# HeatPlates.net
KiCad netlist of a schematic drawn in Altium Designer
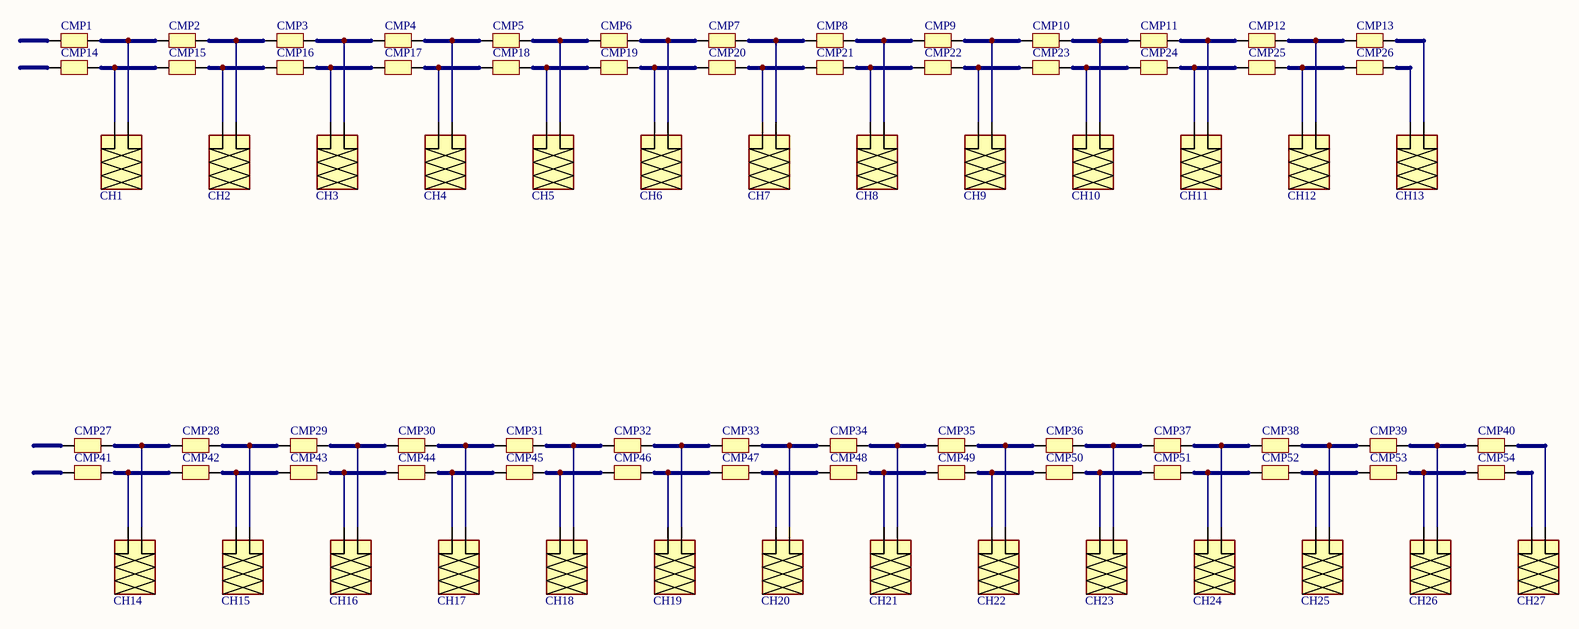
[diagram p0: HeatPlates.SchDoc]

(export (version "E")
  (design (tool "Eeschema 10.0.6"))
  (components
    (comp (ref "CH1")
      (value "GCH")
      (footprint "Generic Cartridge Heater-Footprint-1")
      (description "Generic cartridge heater")
      (libsource (lib "IIT Motorsports") (part "GCH-Symbol-1"))
    )
    (comp (ref "CH2")
      (value "GCH")
      (footprint "Generic Cartridge Heater-Footprint-1")
      (description "Generic cartridge heater")
      (libsource (lib "IIT Motorsports") (part "GCH-Symbol-1"))
    )
    (comp (ref "CH3")
      (value "GCH")
      (footprint "Generic Cartridge Heater-Footprint-1")
      (description "Generic cartridge heater")
      (libsource (lib "IIT Motorsports") (part "GCH-Symbol-1"))
    )
    (comp (ref "CH4")
      (value "GCH")
      (footprint "Generic Cartridge Heater-Footprint-1")
      (description "Generic cartridge heater")
      (libsource (lib "IIT Motorsports") (part "GCH-Symbol-1"))
    )
    (comp (ref "CH5")
      (value "GCH")
      (footprint "Generic Cartridge Heater-Footprint-1")
      (description "Generic cartridge heater")
      (libsource (lib "IIT Motorsports") (part "GCH-Symbol-1"))
    )
    (comp (ref "CH6")
      (value "GCH")
      (footprint "Generic Cartridge Heater-Footprint-1")
      (description "Generic cartridge heater")
      (libsource (lib "IIT Motorsports") (part "GCH-Symbol-1"))
    )
    (comp (ref "CH7")
      (value "GCH")
      (footprint "Generic Cartridge Heater-Footprint-1")
      (description "Generic cartridge heater")
      (libsource (lib "IIT Motorsports") (part "GCH-Symbol-1"))
    )
    (comp (ref "CH8")
      (value "GCH")
      (footprint "Generic Cartridge Heater-Footprint-1")
      (description "Generic cartridge heater")
      (libsource (lib "IIT Motorsports") (part "GCH-Symbol-1"))
    )
    (comp (ref "CH9")
      (value "GCH")
      (footprint "Generic Cartridge Heater-Footprint-1")
      (description "Generic cartridge heater")
      (libsource (lib "IIT Motorsports") (part "GCH-Symbol-1"))
    )
    (comp (ref "CH10")
      (value "GCH")
      (footprint "Generic Cartridge Heater-Footprint-1")
      (description "Generic cartridge heater")
      (libsource (lib "IIT Motorsports") (part "GCH-Symbol-1"))
    )
    (comp (ref "CH11")
      (value "GCH")
      (footprint "Generic Cartridge Heater-Footprint-1")
      (description "Generic cartridge heater")
      (libsource (lib "IIT Motorsports") (part "GCH-Symbol-1"))
    )
    (comp (ref "CH12")
      (value "GCH")
      (footprint "Generic Cartridge Heater-Footprint-1")
      (description "Generic cartridge heater")
      (libsource (lib "IIT Motorsports") (part "GCH-Symbol-1"))
    )
    (comp (ref "CH13")
      (value "GCH")
      (footprint "Generic Cartridge Heater-Footprint-1")
      (description "Generic cartridge heater")
      (libsource (lib "IIT Motorsports") (part "GCH-Symbol-1"))
    )
    (comp (ref "CH14")
      (value "GCH")
      (footprint "Generic Cartridge Heater-Footprint-1")
      (description "Generic cartridge heater")
      (libsource (lib "IIT Motorsports") (part "GCH-Symbol-1"))
    )
    (comp (ref "CH15")
      (value "GCH")
      (footprint "Generic Cartridge Heater-Footprint-1")
      (description "Generic cartridge heater")
      (libsource (lib "IIT Motorsports") (part "GCH-Symbol-1"))
    )
    (comp (ref "CH16")
      (value "GCH")
      (footprint "Generic Cartridge Heater-Footprint-1")
      (description "Generic cartridge heater")
      (libsource (lib "IIT Motorsports") (part "GCH-Symbol-1"))
    )
    (comp (ref "CH17")
      (value "GCH")
      (footprint "Generic Cartridge Heater-Footprint-1")
      (description "Generic cartridge heater")
      (libsource (lib "IIT Motorsports") (part "GCH-Symbol-1"))
    )
    (comp (ref "CH18")
      (value "GCH")
      (footprint "Generic Cartridge Heater-Footprint-1")
      (description "Generic cartridge heater")
      (libsource (lib "IIT Motorsports") (part "GCH-Symbol-1"))
    )
    (comp (ref "CH19")
      (value "GCH")
      (footprint "Generic Cartridge Heater-Footprint-1")
      (description "Generic cartridge heater")
      (libsource (lib "IIT Motorsports") (part "GCH-Symbol-1"))
    )
    (comp (ref "CH20")
      (value "GCH")
      (footprint "Generic Cartridge Heater-Footprint-1")
      (description "Generic cartridge heater")
      (libsource (lib "IIT Motorsports") (part "GCH-Symbol-1"))
    )
    (comp (ref "CH21")
      (value "GCH")
      (footprint "Generic Cartridge Heater-Footprint-1")
      (description "Generic cartridge heater")
      (libsource (lib "IIT Motorsports") (part "GCH-Symbol-1"))
    )
    (comp (ref "CH22")
      (value "GCH")
      (footprint "Generic Cartridge Heater-Footprint-1")
      (description "Generic cartridge heater")
      (libsource (lib "IIT Motorsports") (part "GCH-Symbol-1"))
    )
    (comp (ref "CH23")
      (value "GCH")
      (footprint "Generic Cartridge Heater-Footprint-1")
      (description "Generic cartridge heater")
      (libsource (lib "IIT Motorsports") (part "GCH-Symbol-1"))
    )
    (comp (ref "CH24")
      (value "GCH")
      (footprint "Generic Cartridge Heater-Footprint-1")
      (description "Generic cartridge heater")
      (libsource (lib "IIT Motorsports") (part "GCH-Symbol-1"))
    )
    (comp (ref "CH25")
      (value "GCH")
      (footprint "Generic Cartridge Heater-Footprint-1")
      (description "Generic cartridge heater")
      (libsource (lib "IIT Motorsports") (part "GCH-Symbol-1"))
    )
    (comp (ref "CH26")
      (value "GCH")
      (footprint "Generic Cartridge Heater-Footprint-1")
      (description "Generic cartridge heater")
      (libsource (lib "IIT Motorsports") (part "GCH-Symbol-1"))
    )
    (comp (ref "CH27")
      (value "GCH")
      (footprint "Generic Cartridge Heater-Footprint-1")
      (description "Generic cartridge heater")
      (libsource (lib "IIT Motorsports") (part "GCH-Symbol-1"))
    )
    (comp (ref "CMP1")
      (value "0192020054")
      (footprint "0192020054-Footprint-1")
      (libsource (lib "IIT Motorsports") (part "0192020054-Symbol-1"))
    )
    (comp (ref "CMP2")
      (value "0192020054")
      (footprint "0192020054-Footprint-1")
      (libsource (lib "IIT Motorsports") (part "0192020054-Symbol-1"))
    )
    (comp (ref "CMP3")
      (value "0192020054")
      (footprint "0192020054-Footprint-1")
      (libsource (lib "IIT Motorsports") (part "0192020054-Symbol-1"))
    )
    (comp (ref "CMP4")
      (value "0192020054")
      (footprint "0192020054-Footprint-1")
      (libsource (lib "IIT Motorsports") (part "0192020054-Symbol-1"))
    )
    (comp (ref "CMP5")
      (value "0192020054")
      (footprint "0192020054-Footprint-1")
      (libsource (lib "IIT Motorsports") (part "0192020054-Symbol-1"))
    )
    (comp (ref "CMP6")
      (value "0192020054")
      (footprint "0192020054-Footprint-1")
      (libsource (lib "IIT Motorsports") (part "0192020054-Symbol-1"))
    )
    (comp (ref "CMP7")
      (value "0192020054")
      (footprint "0192020054-Footprint-1")
      (libsource (lib "IIT Motorsports") (part "0192020054-Symbol-1"))
    )
    (comp (ref "CMP8")
      (value "0192020054")
      (footprint "0192020054-Footprint-1")
      (libsource (lib "IIT Motorsports") (part "0192020054-Symbol-1"))
    )
    (comp (ref "CMP9")
      (value "0192020054")
      (footprint "0192020054-Footprint-1")
      (libsource (lib "IIT Motorsports") (part "0192020054-Symbol-1"))
    )
    (comp (ref "CMP10")
      (value "0192020054")
      (footprint "0192020054-Footprint-1")
      (libsource (lib "IIT Motorsports") (part "0192020054-Symbol-1"))
    )
    (comp (ref "CMP11")
      (value "0192020054")
      (footprint "0192020054-Footprint-1")
      (libsource (lib "IIT Motorsports") (part "0192020054-Symbol-1"))
    )
    (comp (ref "CMP12")
      (value "0192020054")
      (footprint "0192020054-Footprint-1")
      (libsource (lib "IIT Motorsports") (part "0192020054-Symbol-1"))
    )
    (comp (ref "CMP13")
      (value "0192020054")
      (footprint "0192020054-Footprint-1")
      (libsource (lib "IIT Motorsports") (part "0192020054-Symbol-1"))
    )
    (comp (ref "CMP14")
      (value "0192020054")
      (footprint "0192020054-Footprint-1")
      (libsource (lib "IIT Motorsports") (part "0192020054-Symbol-1"))
    )
    (comp (ref "CMP15")
      (value "0192020054")
      (footprint "0192020054-Footprint-1")
      (libsource (lib "IIT Motorsports") (part "0192020054-Symbol-1"))
    )
    (comp (ref "CMP16")
      (value "0192020054")
      (footprint "0192020054-Footprint-1")
      (libsource (lib "IIT Motorsports") (part "0192020054-Symbol-1"))
    )
    (comp (ref "CMP17")
      (value "0192020054")
      (footprint "0192020054-Footprint-1")
      (libsource (lib "IIT Motorsports") (part "0192020054-Symbol-1"))
    )
    (comp (ref "CMP18")
      (value "0192020054")
      (footprint "0192020054-Footprint-1")
      (libsource (lib "IIT Motorsports") (part "0192020054-Symbol-1"))
    )
    (comp (ref "CMP19")
      (value "0192020054")
      (footprint "0192020054-Footprint-1")
      (libsource (lib "IIT Motorsports") (part "0192020054-Symbol-1"))
    )
    (comp (ref "CMP20")
      (value "0192020054")
      (footprint "0192020054-Footprint-1")
      (libsource (lib "IIT Motorsports") (part "0192020054-Symbol-1"))
    )
    (comp (ref "CMP21")
      (value "0192020054")
      (footprint "0192020054-Footprint-1")
      (libsource (lib "IIT Motorsports") (part "0192020054-Symbol-1"))
    )
    (comp (ref "CMP22")
      (value "0192020054")
      (footprint "0192020054-Footprint-1")
      (libsource (lib "IIT Motorsports") (part "0192020054-Symbol-1"))
    )
    (comp (ref "CMP23")
      (value "0192020054")
      (footprint "0192020054-Footprint-1")
      (libsource (lib "IIT Motorsports") (part "0192020054-Symbol-1"))
    )
    (comp (ref "CMP24")
      (value "0192020054")
      (footprint "0192020054-Footprint-1")
      (libsource (lib "IIT Motorsports") (part "0192020054-Symbol-1"))
    )
    (comp (ref "CMP25")
      (value "0192020054")
      (footprint "0192020054-Footprint-1")
      (libsource (lib "IIT Motorsports") (part "0192020054-Symbol-1"))
    )
    (comp (ref "CMP26")
      (value "0192020054")
      (footprint "0192020054-Footprint-1")
      (libsource (lib "IIT Motorsports") (part "0192020054-Symbol-1"))
    )
    (comp (ref "CMP27")
      (value "0192020054")
      (footprint "0192020054-Footprint-1")
      (libsource (lib "IIT Motorsports") (part "0192020054-Symbol-1"))
    )
    (comp (ref "CMP28")
      (value "0192020054")
      (footprint "0192020054-Footprint-1")
      (libsource (lib "IIT Motorsports") (part "0192020054-Symbol-1"))
    )
    (comp (ref "CMP29")
      (value "0192020054")
      (footprint "0192020054-Footprint-1")
      (libsource (lib "IIT Motorsports") (part "0192020054-Symbol-1"))
    )
    (comp (ref "CMP30")
      (value "0192020054")
      (footprint "0192020054-Footprint-1")
      (libsource (lib "IIT Motorsports") (part "0192020054-Symbol-1"))
    )
    (comp (ref "CMP31")
      (value "0192020054")
      (footprint "0192020054-Footprint-1")
      (libsource (lib "IIT Motorsports") (part "0192020054-Symbol-1"))
    )
    (comp (ref "CMP32")
      (value "0192020054")
      (footprint "0192020054-Footprint-1")
      (libsource (lib "IIT Motorsports") (part "0192020054-Symbol-1"))
    )
    (comp (ref "CMP33")
      (value "0192020054")
      (footprint "0192020054-Footprint-1")
      (libsource (lib "IIT Motorsports") (part "0192020054-Symbol-1"))
    )
    (comp (ref "CMP34")
      (value "0192020054")
      (footprint "0192020054-Footprint-1")
      (libsource (lib "IIT Motorsports") (part "0192020054-Symbol-1"))
    )
    (comp (ref "CMP35")
      (value "0192020054")
      (footprint "0192020054-Footprint-1")
      (libsource (lib "IIT Motorsports") (part "0192020054-Symbol-1"))
    )
    (comp (ref "CMP36")
      (value "0192020054")
      (footprint "0192020054-Footprint-1")
      (libsource (lib "IIT Motorsports") (part "0192020054-Symbol-1"))
    )
    (comp (ref "CMP37")
      (value "0192020054")
      (footprint "0192020054-Footprint-1")
      (libsource (lib "IIT Motorsports") (part "0192020054-Symbol-1"))
    )
    (comp (ref "CMP38")
      (value "0192020054")
      (footprint "0192020054-Footprint-1")
      (libsource (lib "IIT Motorsports") (part "0192020054-Symbol-1"))
    )
    (comp (ref "CMP39")
      (value "0192020054")
      (footprint "0192020054-Footprint-1")
      (libsource (lib "IIT Motorsports") (part "0192020054-Symbol-1"))
    )
    (comp (ref "CMP40")
      (value "0192020054")
      (footprint "0192020054-Footprint-1")
      (libsource (lib "IIT Motorsports") (part "0192020054-Symbol-1"))
    )
    (comp (ref "CMP41")
      (value "0192020054")
      (footprint "0192020054-Footprint-1")
      (libsource (lib "IIT Motorsports") (part "0192020054-Symbol-1"))
    )
    (comp (ref "CMP42")
      (value "0192020054")
      (footprint "0192020054-Footprint-1")
      (libsource (lib "IIT Motorsports") (part "0192020054-Symbol-1"))
    )
    (comp (ref "CMP43")
      (value "0192020054")
      (footprint "0192020054-Footprint-1")
      (libsource (lib "IIT Motorsports") (part "0192020054-Symbol-1"))
    )
    (comp (ref "CMP44")
      (value "0192020054")
      (footprint "0192020054-Footprint-1")
      (libsource (lib "IIT Motorsports") (part "0192020054-Symbol-1"))
    )
    (comp (ref "CMP45")
      (value "0192020054")
      (footprint "0192020054-Footprint-1")
      (libsource (lib "IIT Motorsports") (part "0192020054-Symbol-1"))
    )
    (comp (ref "CMP46")
      (value "0192020054")
      (footprint "0192020054-Footprint-1")
      (libsource (lib "IIT Motorsports") (part "0192020054-Symbol-1"))
    )
    (comp (ref "CMP47")
      (value "0192020054")
      (footprint "0192020054-Footprint-1")
      (libsource (lib "IIT Motorsports") (part "0192020054-Symbol-1"))
    )
    (comp (ref "CMP48")
      (value "0192020054")
      (footprint "0192020054-Footprint-1")
      (libsource (lib "IIT Motorsports") (part "0192020054-Symbol-1"))
    )
    (comp (ref "CMP49")
      (value "0192020054")
      (footprint "0192020054-Footprint-1")
      (libsource (lib "IIT Motorsports") (part "0192020054-Symbol-1"))
    )
    (comp (ref "CMP50")
      (value "0192020054")
      (footprint "0192020054-Footprint-1")
      (libsource (lib "IIT Motorsports") (part "0192020054-Symbol-1"))
    )
    (comp (ref "CMP51")
      (value "0192020054")
      (footprint "0192020054-Footprint-1")
      (libsource (lib "IIT Motorsports") (part "0192020054-Symbol-1"))
    )
    (comp (ref "CMP52")
      (value "0192020054")
      (footprint "0192020054-Footprint-1")
      (libsource (lib "IIT Motorsports") (part "0192020054-Symbol-1"))
    )
    (comp (ref "CMP53")
      (value "0192020054")
      (footprint "0192020054-Footprint-1")
      (libsource (lib "IIT Motorsports") (part "0192020054-Symbol-1"))
    )
    (comp (ref "CMP54")
      (value "0192020054")
      (footprint "0192020054-Footprint-1")
      (libsource (lib "IIT Motorsports") (part "0192020054-Symbol-1"))
    )
  )
  (nets
    (net (code "1") (name "Net-(CH1-Pad0)") (class "Default")
      (node (ref "CH1") (pin "0") (pinfunction "0_0") (pintype "passive"))
      (node (ref "CMP14") (pin "1") (pinfunction "1_1") (pintype "passive"))
      (node (ref "CMP15") (pin "0") (pinfunction "0_0") (pintype "passive"))
    )
    (net (code "2") (name "Net-(CH1-Pad1)") (class "Default")
      (node (ref "CH1") (pin "1") (pinfunction "1_1") (pintype "passive"))
      (node (ref "CMP1") (pin "1") (pinfunction "1_1") (pintype "passive"))
      (node (ref "CMP2") (pin "0") (pinfunction "0_0") (pintype "passive"))
    )
    (net (code "3") (name "Net-(CH2-Pad0)") (class "Default")
      (node (ref "CH2") (pin "0") (pinfunction "0_0") (pintype "passive"))
      (node (ref "CMP15") (pin "1") (pinfunction "1_1") (pintype "passive"))
      (node (ref "CMP16") (pin "0") (pinfunction "0_0") (pintype "passive"))
    )
    (net (code "4") (name "Net-(CH2-Pad1)") (class "Default")
      (node (ref "CH2") (pin "1") (pinfunction "1_1") (pintype "passive"))
      (node (ref "CMP2") (pin "1") (pinfunction "1_1") (pintype "passive"))
      (node (ref "CMP3") (pin "0") (pinfunction "0_0") (pintype "passive"))
    )
    (net (code "5") (name "Net-(CH3-Pad0)") (class "Default")
      (node (ref "CH3") (pin "0") (pinfunction "0_0") (pintype "passive"))
      (node (ref "CMP16") (pin "1") (pinfunction "1_1") (pintype "passive"))
      (node (ref "CMP17") (pin "0") (pinfunction "0_0") (pintype "passive"))
    )
    (net (code "6") (name "Net-(CH3-Pad1)") (class "Default")
      (node (ref "CH3") (pin "1") (pinfunction "1_1") (pintype "passive"))
      (node (ref "CMP3") (pin "1") (pinfunction "1_1") (pintype "passive"))
      (node (ref "CMP4") (pin "0") (pinfunction "0_0") (pintype "passive"))
    )
    (net (code "7") (name "Net-(CH4-Pad0)") (class "Default")
      (node (ref "CH4") (pin "0") (pinfunction "0_0") (pintype "passive"))
      (node (ref "CMP17") (pin "1") (pinfunction "1_1") (pintype "passive"))
      (node (ref "CMP18") (pin "0") (pinfunction "0_0") (pintype "passive"))
    )
    (net (code "8") (name "Net-(CH4-Pad1)") (class "Default")
      (node (ref "CH4") (pin "1") (pinfunction "1_1") (pintype "passive"))
      (node (ref "CMP4") (pin "1") (pinfunction "1_1") (pintype "passive"))
      (node (ref "CMP5") (pin "0") (pinfunction "0_0") (pintype "passive"))
    )
    (net (code "9") (name "Net-(CH5-Pad0)") (class "Default")
      (node (ref "CH5") (pin "0") (pinfunction "0_0") (pintype "passive"))
      (node (ref "CMP18") (pin "1") (pinfunction "1_1") (pintype "passive"))
      (node (ref "CMP19") (pin "0") (pinfunction "0_0") (pintype "passive"))
    )
    (net (code "10") (name "Net-(CH5-Pad1)") (class "Default")
      (node (ref "CH5") (pin "1") (pinfunction "1_1") (pintype "passive"))
      (node (ref "CMP5") (pin "1") (pinfunction "1_1") (pintype "passive"))
      (node (ref "CMP6") (pin "0") (pinfunction "0_0") (pintype "passive"))
    )
    (net (code "11") (name "Net-(CH6-Pad0)") (class "Default")
      (node (ref "CH6") (pin "0") (pinfunction "0_0") (pintype "passive"))
      (node (ref "CMP19") (pin "1") (pinfunction "1_1") (pintype "passive"))
      (node (ref "CMP20") (pin "0") (pinfunction "0_0") (pintype "passive"))
    )
    (net (code "12") (name "Net-(CH6-Pad1)") (class "Default")
      (node (ref "CH6") (pin "1") (pinfunction "1_1") (pintype "passive"))
      (node (ref "CMP6") (pin "1") (pinfunction "1_1") (pintype "passive"))
      (node (ref "CMP7") (pin "0") (pinfunction "0_0") (pintype "passive"))
    )
    (net (code "13") (name "Net-(CH7-Pad0)") (class "Default")
      (node (ref "CH7") (pin "0") (pinfunction "0_0") (pintype "passive"))
      (node (ref "CMP20") (pin "1") (pinfunction "1_1") (pintype "passive"))
      (node (ref "CMP21") (pin "0") (pinfunction "0_0") (pintype "passive"))
    )
    (net (code "14") (name "Net-(CH7-Pad1)") (class "Default")
      (node (ref "CH7") (pin "1") (pinfunction "1_1") (pintype "passive"))
      (node (ref "CMP7") (pin "1") (pinfunction "1_1") (pintype "passive"))
      (node (ref "CMP8") (pin "0") (pinfunction "0_0") (pintype "passive"))
    )
    (net (code "15") (name "Net-(CH8-Pad0)") (class "Default")
      (node (ref "CH8") (pin "0") (pinfunction "0_0") (pintype "passive"))
      (node (ref "CMP21") (pin "1") (pinfunction "1_1") (pintype "passive"))
      (node (ref "CMP22") (pin "0") (pinfunction "0_0") (pintype "passive"))
    )
    (net (code "16") (name "Net-(CH8-Pad1)") (class "Default")
      (node (ref "CH8") (pin "1") (pinfunction "1_1") (pintype "passive"))
      (node (ref "CMP8") (pin "1") (pinfunction "1_1") (pintype "passive"))
      (node (ref "CMP9") (pin "0") (pinfunction "0_0") (pintype "passive"))
    )
    (net (code "17") (name "Net-(CH9-Pad0)") (class "Default")
      (node (ref "CH9") (pin "0") (pinfunction "0_0") (pintype "passive"))
      (node (ref "CMP22") (pin "1") (pinfunction "1_1") (pintype "passive"))
      (node (ref "CMP23") (pin "0") (pinfunction "0_0") (pintype "passive"))
    )
    (net (code "18") (name "Net-(CH9-Pad1)") (class "Default")
      (node (ref "CH9") (pin "1") (pinfunction "1_1") (pintype "passive"))
      (node (ref "CMP10") (pin "0") (pinfunction "0_0") (pintype "passive"))
      (node (ref "CMP9") (pin "1") (pinfunction "1_1") (pintype "passive"))
    )
    (net (code "19") (name "Net-(CH10-Pad0)") (class "Default")
      (node (ref "CH10") (pin "0") (pinfunction "0_0") (pintype "passive"))
      (node (ref "CMP23") (pin "1") (pinfunction "1_1") (pintype "passive"))
      (node (ref "CMP24") (pin "0") (pinfunction "0_0") (pintype "passive"))
    )
    (net (code "20") (name "Net-(CH10-Pad1)") (class "Default")
      (node (ref "CH10") (pin "1") (pinfunction "1_1") (pintype "passive"))
      (node (ref "CMP10") (pin "1") (pinfunction "1_1") (pintype "passive"))
      (node (ref "CMP11") (pin "0") (pinfunction "0_0") (pintype "passive"))
    )
    (net (code "21") (name "Net-(CH11-Pad0)") (class "Default")
      (node (ref "CH11") (pin "0") (pinfunction "0_0") (pintype "passive"))
      (node (ref "CMP24") (pin "1") (pinfunction "1_1") (pintype "passive"))
      (node (ref "CMP25") (pin "0") (pinfunction "0_0") (pintype "passive"))
    )
    (net (code "22") (name "Net-(CH11-Pad1)") (class "Default")
      (node (ref "CH11") (pin "1") (pinfunction "1_1") (pintype "passive"))
      (node (ref "CMP11") (pin "1") (pinfunction "1_1") (pintype "passive"))
      (node (ref "CMP12") (pin "0") (pinfunction "0_0") (pintype "passive"))
    )
    (net (code "23") (name "Net-(CH12-Pad0)") (class "Default")
      (node (ref "CH12") (pin "0") (pinfunction "0_0") (pintype "passive"))
      (node (ref "CMP25") (pin "1") (pinfunction "1_1") (pintype "passive"))
      (node (ref "CMP26") (pin "0") (pinfunction "0_0") (pintype "passive"))
    )
    (net (code "24") (name "Net-(CH12-Pad1)") (class "Default")
      (node (ref "CH12") (pin "1") (pinfunction "1_1") (pintype "passive"))
      (node (ref "CMP12") (pin "1") (pinfunction "1_1") (pintype "passive"))
      (node (ref "CMP13") (pin "0") (pinfunction "0_0") (pintype "passive"))
    )
    (net (code "25") (name "Net-(CH13-Pad0)") (class "Default")
      (node (ref "CH13") (pin "0") (pinfunction "0_0") (pintype "passive"))
      (node (ref "CMP26") (pin "1") (pinfunction "1_1") (pintype "passive"))
    )
    (net (code "26") (name "Net-(CH13-Pad1)") (class "Default")
      (node (ref "CH13") (pin "1") (pinfunction "1_1") (pintype "passive"))
      (node (ref "CMP13") (pin "1") (pinfunction "1_1") (pintype "passive"))
    )
    (net (code "27") (name "Net-(CH14-Pad0)") (class "Default")
      (node (ref "CH14") (pin "0") (pinfunction "0_0") (pintype "passive"))
      (node (ref "CMP41") (pin "1") (pinfunction "1_1") (pintype "passive"))
      (node (ref "CMP42") (pin "0") (pinfunction "0_0") (pintype "passive"))
    )
    (net (code "28") (name "Net-(CH14-Pad1)") (class "Default")
      (node (ref "CH14") (pin "1") (pinfunction "1_1") (pintype "passive"))
      (node (ref "CMP27") (pin "1") (pinfunction "1_1") (pintype "passive"))
      (node (ref "CMP28") (pin "0") (pinfunction "0_0") (pintype "passive"))
    )
    (net (code "29") (name "Net-(CH15-Pad0)") (class "Default")
      (node (ref "CH15") (pin "0") (pinfunction "0_0") (pintype "passive"))
      (node (ref "CMP42") (pin "1") (pinfunction "1_1") (pintype "passive"))
      (node (ref "CMP43") (pin "0") (pinfunction "0_0") (pintype "passive"))
    )
    (net (code "30") (name "Net-(CH15-Pad1)") (class "Default")
      (node (ref "CH15") (pin "1") (pinfunction "1_1") (pintype "passive"))
      (node (ref "CMP28") (pin "1") (pinfunction "1_1") (pintype "passive"))
      (node (ref "CMP29") (pin "0") (pinfunction "0_0") (pintype "passive"))
    )
    (net (code "31") (name "Net-(CH16-Pad0)") (class "Default")
      (node (ref "CH16") (pin "0") (pinfunction "0_0") (pintype "passive"))
      (node (ref "CMP43") (pin "1") (pinfunction "1_1") (pintype "passive"))
      (node (ref "CMP44") (pin "0") (pinfunction "0_0") (pintype "passive"))
    )
    (net (code "32") (name "Net-(CH16-Pad1)") (class "Default")
      (node (ref "CH16") (pin "1") (pinfunction "1_1") (pintype "passive"))
      (node (ref "CMP29") (pin "1") (pinfunction "1_1") (pintype "passive"))
      (node (ref "CMP30") (pin "0") (pinfunction "0_0") (pintype "passive"))
    )
    (net (code "33") (name "Net-(CH17-Pad0)") (class "Default")
      (node (ref "CH17") (pin "0") (pinfunction "0_0") (pintype "passive"))
      (node (ref "CMP44") (pin "1") (pinfunction "1_1") (pintype "passive"))
      (node (ref "CMP45") (pin "0") (pinfunction "0_0") (pintype "passive"))
    )
    (net (code "34") (name "Net-(CH17-Pad1)") (class "Default")
      (node (ref "CH17") (pin "1") (pinfunction "1_1") (pintype "passive"))
      (node (ref "CMP30") (pin "1") (pinfunction "1_1") (pintype "passive"))
      (node (ref "CMP31") (pin "0") (pinfunction "0_0") (pintype "passive"))
    )
    (net (code "35") (name "Net-(CH18-Pad0)") (class "Default")
      (node (ref "CH18") (pin "0") (pinfunction "0_0") (pintype "passive"))
      (node (ref "CMP45") (pin "1") (pinfunction "1_1") (pintype "passive"))
      (node (ref "CMP46") (pin "0") (pinfunction "0_0") (pintype "passive"))
    )
    (net (code "36") (name "Net-(CH18-Pad1)") (class "Default")
      (node (ref "CH18") (pin "1") (pinfunction "1_1") (pintype "passive"))
      (node (ref "CMP31") (pin "1") (pinfunction "1_1") (pintype "passive"))
      (node (ref "CMP32") (pin "0") (pinfunction "0_0") (pintype "passive"))
    )
    (net (code "37") (name "Net-(CH19-Pad0)") (class "Default")
      (node (ref "CH19") (pin "0") (pinfunction "0_0") (pintype "passive"))
      (node (ref "CMP46") (pin "1") (pinfunction "1_1") (pintype "passive"))
      (node (ref "CMP47") (pin "0") (pinfunction "0_0") (pintype "passive"))
    )
    (net (code "38") (name "Net-(CH19-Pad1)") (class "Default")
      (node (ref "CH19") (pin "1") (pinfunction "1_1") (pintype "passive"))
      (node (ref "CMP32") (pin "1") (pinfunction "1_1") (pintype "passive"))
      (node (ref "CMP33") (pin "0") (pinfunction "0_0") (pintype "passive"))
    )
    (net (code "39") (name "Net-(CH20-Pad0)") (class "Default")
      (node (ref "CH20") (pin "0") (pinfunction "0_0") (pintype "passive"))
      (node (ref "CMP47") (pin "1") (pinfunction "1_1") (pintype "passive"))
      (node (ref "CMP48") (pin "0") (pinfunction "0_0") (pintype "passive"))
    )
    (net (code "40") (name "Net-(CH20-Pad1)") (class "Default")
      (node (ref "CH20") (pin "1") (pinfunction "1_1") (pintype "passive"))
      (node (ref "CMP33") (pin "1") (pinfunction "1_1") (pintype "passive"))
      (node (ref "CMP34") (pin "0") (pinfunction "0_0") (pintype "passive"))
    )
    (net (code "41") (name "Net-(CH21-Pad0)") (class "Default")
      (node (ref "CH21") (pin "0") (pinfunction "0_0") (pintype "passive"))
      (node (ref "CMP48") (pin "1") (pinfunction "1_1") (pintype "passive"))
      (node (ref "CMP49") (pin "0") (pinfunction "0_0") (pintype "passive"))
    )
    (net (code "42") (name "Net-(CH21-Pad1)") (class "Default")
      (node (ref "CH21") (pin "1") (pinfunction "1_1") (pintype "passive"))
      (node (ref "CMP34") (pin "1") (pinfunction "1_1") (pintype "passive"))
      (node (ref "CMP35") (pin "0") (pinfunction "0_0") (pintype "passive"))
    )
    (net (code "43") (name "Net-(CH22-Pad0)") (class "Default")
      (node (ref "CH22") (pin "0") (pinfunction "0_0") (pintype "passive"))
      (node (ref "CMP49") (pin "1") (pinfunction "1_1") (pintype "passive"))
      (node (ref "CMP50") (pin "0") (pinfunction "0_0") (pintype "passive"))
    )
    (net (code "44") (name "Net-(CH22-Pad1)") (class "Default")
      (node (ref "CH22") (pin "1") (pinfunction "1_1") (pintype "passive"))
      (node (ref "CMP35") (pin "1") (pinfunction "1_1") (pintype "passive"))
      (node (ref "CMP36") (pin "0") (pinfunction "0_0") (pintype "passive"))
    )
    (net (code "45") (name "Net-(CH23-Pad0)") (class "Default")
      (node (ref "CH23") (pin "0") (pinfunction "0_0") (pintype "passive"))
      (node (ref "CMP50") (pin "1") (pinfunction "1_1") (pintype "passive"))
      (node (ref "CMP51") (pin "0") (pinfunction "0_0") (pintype "passive"))
    )
    (net (code "46") (name "Net-(CH23-Pad1)") (class "Default")
      (node (ref "CH23") (pin "1") (pinfunction "1_1") (pintype "passive"))
      (node (ref "CMP36") (pin "1") (pinfunction "1_1") (pintype "passive"))
      (node (ref "CMP37") (pin "0") (pinfunction "0_0") (pintype "passive"))
    )
    (net (code "47") (name "Net-(CH24-Pad0)") (class "Default")
      (node (ref "CH24") (pin "0") (pinfunction "0_0") (pintype "passive"))
      (node (ref "CMP51") (pin "1") (pinfunction "1_1") (pintype "passive"))
      (node (ref "CMP52") (pin "0") (pinfunction "0_0") (pintype "passive"))
    )
    (net (code "48") (name "Net-(CH24-Pad1)") (class "Default")
      (node (ref "CH24") (pin "1") (pinfunction "1_1") (pintype "passive"))
      (node (ref "CMP37") (pin "1") (pinfunction "1_1") (pintype "passive"))
      (node (ref "CMP38") (pin "0") (pinfunction "0_0") (pintype "passive"))
    )
    (net (code "49") (name "Net-(CH25-Pad0)") (class "Default")
      (node (ref "CH25") (pin "0") (pinfunction "0_0") (pintype "passive"))
      (node (ref "CMP52") (pin "1") (pinfunction "1_1") (pintype "passive"))
      (node (ref "CMP53") (pin "0") (pinfunction "0_0") (pintype "passive"))
    )
    (net (code "50") (name "Net-(CH25-Pad1)") (class "Default")
      (node (ref "CH25") (pin "1") (pinfunction "1_1") (pintype "passive"))
      (node (ref "CMP38") (pin "1") (pinfunction "1_1") (pintype "passive"))
      (node (ref "CMP39") (pin "0") (pinfunction "0_0") (pintype "passive"))
    )
    (net (code "51") (name "Net-(CH26-Pad0)") (class "Default")
      (node (ref "CH26") (pin "0") (pinfunction "0_0") (pintype "passive"))
      (node (ref "CMP53") (pin "1") (pinfunction "1_1") (pintype "passive"))
      (node (ref "CMP54") (pin "0") (pinfunction "0_0") (pintype "passive"))
    )
    (net (code "52") (name "Net-(CH26-Pad1)") (class "Default")
      (node (ref "CH26") (pin "1") (pinfunction "1_1") (pintype "passive"))
      (node (ref "CMP39") (pin "1") (pinfunction "1_1") (pintype "passive"))
      (node (ref "CMP40") (pin "0") (pinfunction "0_0") (pintype "passive"))
    )
    (net (code "53") (name "Net-(CH27-Pad0)") (class "Default")
      (node (ref "CH27") (pin "0") (pinfunction "0_0") (pintype "passive"))
      (node (ref "CMP54") (pin "1") (pinfunction "1_1") (pintype "passive"))
    )
    (net (code "54") (name "Net-(CH27-Pad1)") (class "Default")
      (node (ref "CH27") (pin "1") (pinfunction "1_1") (pintype "passive"))
      (node (ref "CMP40") (pin "1") (pinfunction "1_1") (pintype "passive"))
    )
    (net (code "55") (name "unconnected-(CMP1-Pad0)") (class "Default")
      (node (ref "CMP1") (pin "0") (pinfunction "0_0") (pintype "passive"))
    )
    (net (code "56") (name "unconnected-(CMP14-Pad0)") (class "Default")
      (node (ref "CMP14") (pin "0") (pinfunction "0_0") (pintype "passive"))
    )
    (net (code "57") (name "unconnected-(CMP27-Pad0)") (class "Default")
      (node (ref "CMP27") (pin "0") (pinfunction "0_0") (pintype "passive"))
    )
    (net (code "58") (name "unconnected-(CMP41-Pad0)") (class "Default")
      (node (ref "CMP41") (pin "0") (pinfunction "0_0") (pintype "passive"))
    )
  )
)
